# HalfMegCoCo.net
KiCad netlist of a schematic drawn in EAGLE
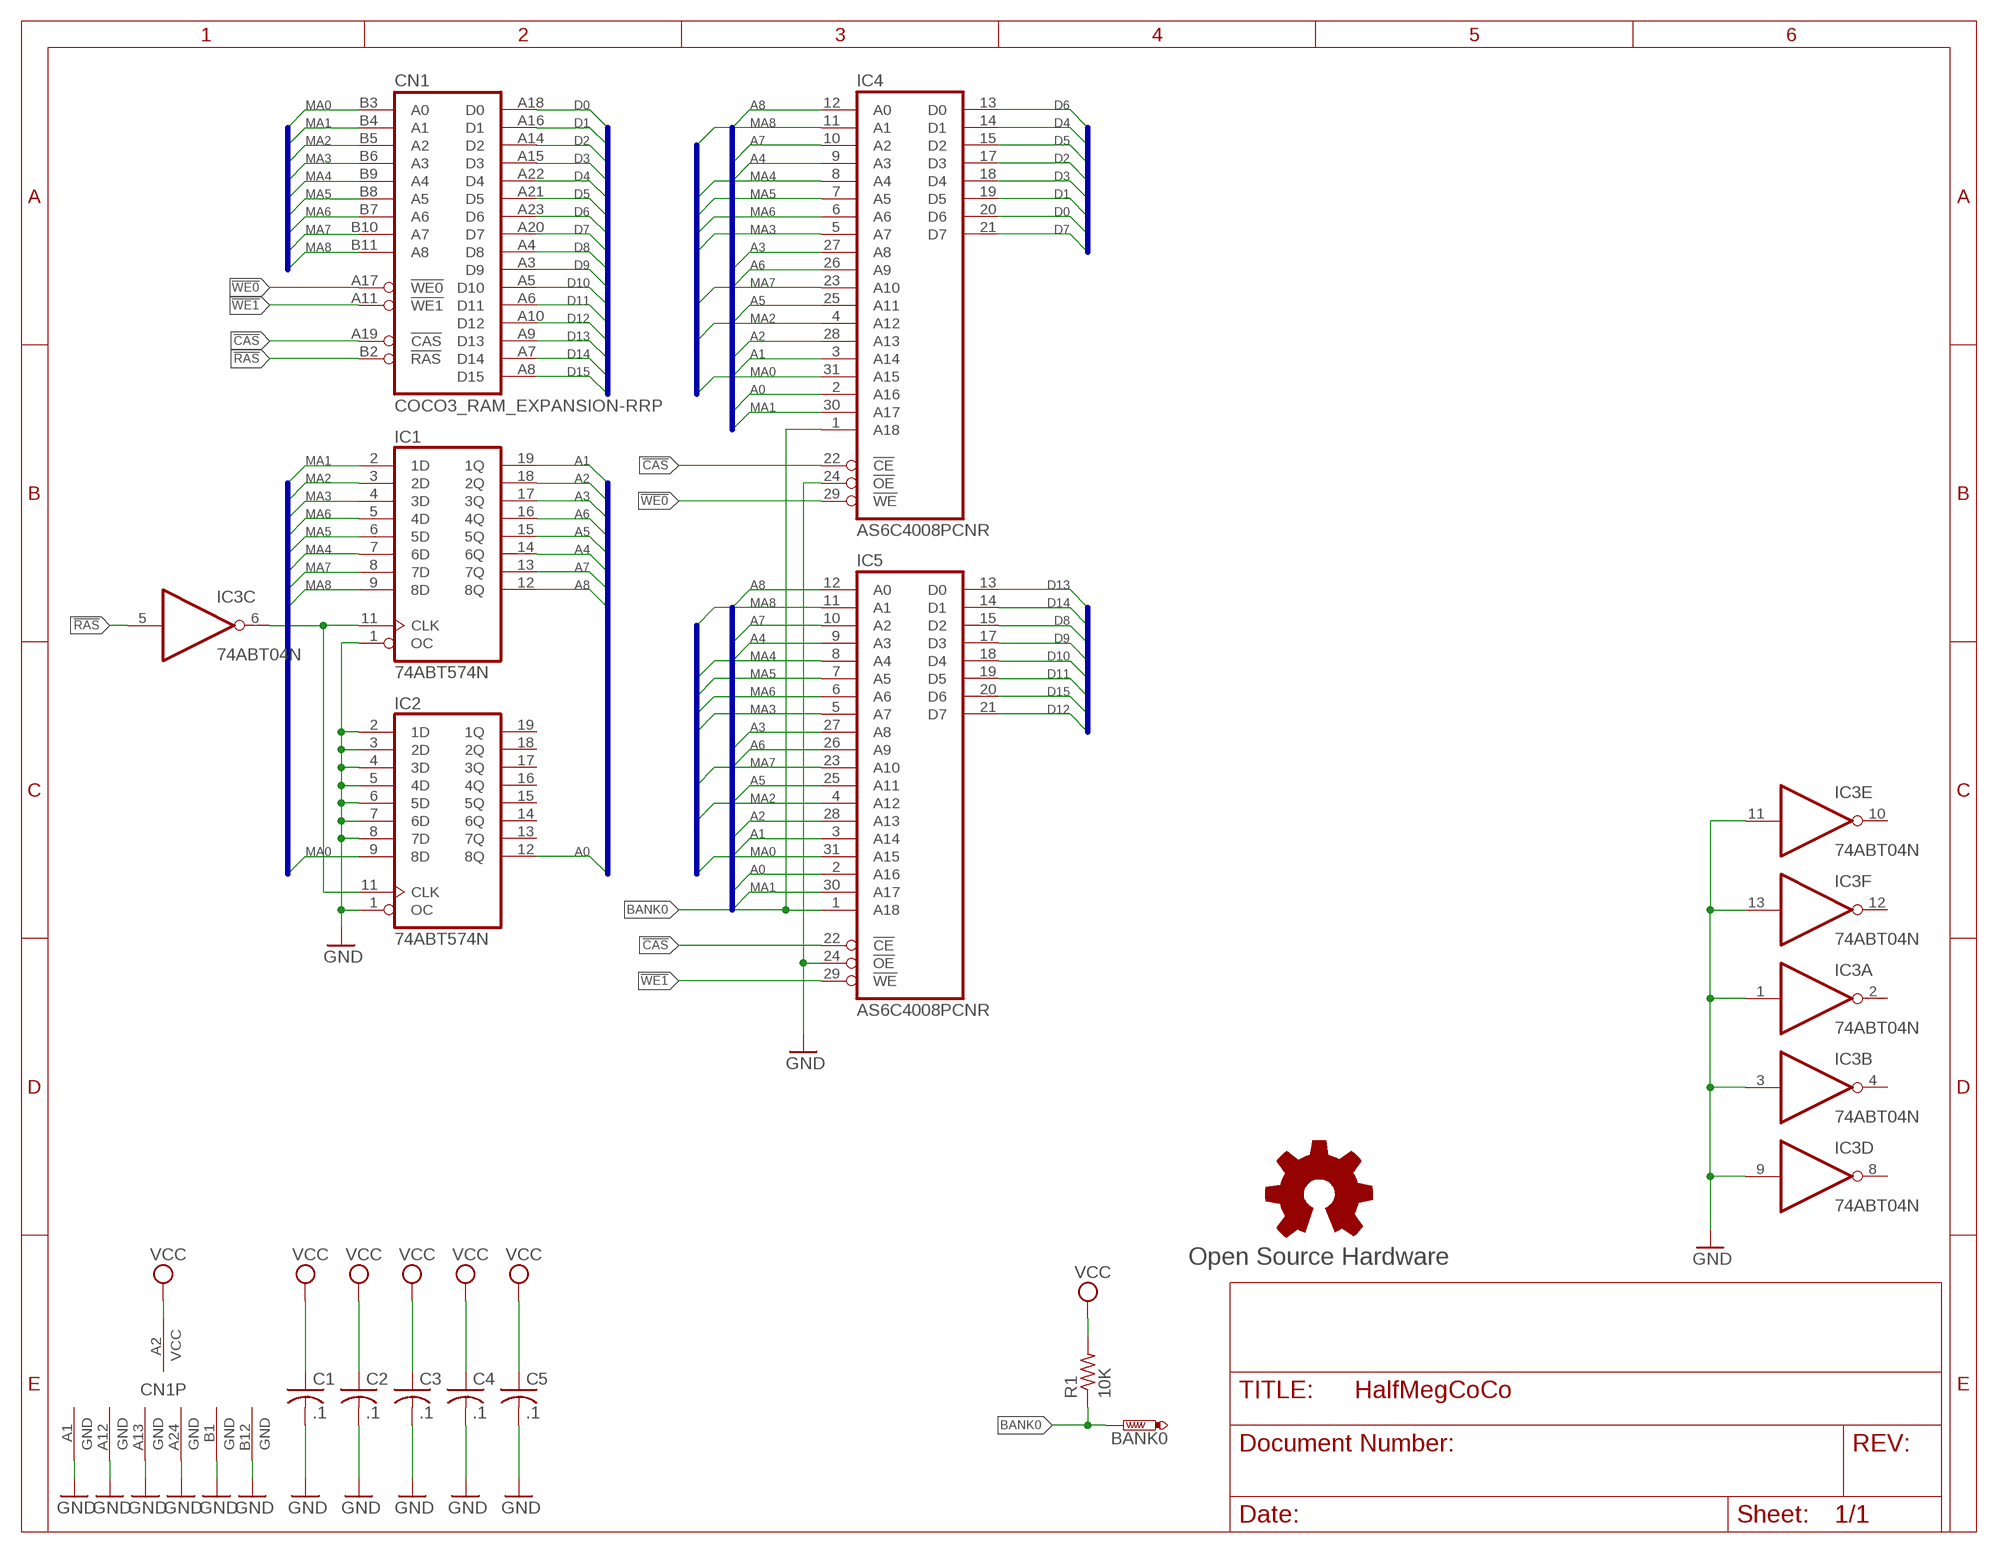
[diagram p0: schematic, sheet 1]

(export (version "E")
  (design (tool "Eeschema 10.0.6"))
  (components
    (comp (ref "BANK0")
      (value "PTR1PAD1-13")
      (footprint "eagle-import:P1-13")
      (libsource (lib "eagle-import") (part "PTR1PAD1-13"))
    )
    (comp (ref "C1")
      (value ".1")
      (footprint "eagle-import:C025-025X050")
      (libsource (lib "eagle-import") (part "C-US025-025X050"))
    )
    (comp (ref "C2")
      (value ".1")
      (footprint "eagle-import:C025-025X050")
      (libsource (lib "eagle-import") (part "C-US025-025X050"))
    )
    (comp (ref "C3")
      (value ".1")
      (footprint "eagle-import:C025-025X050")
      (libsource (lib "eagle-import") (part "C-US025-025X050"))
    )
    (comp (ref "C4")
      (value ".1")
      (footprint "eagle-import:C025-025X050")
      (libsource (lib "eagle-import") (part "C-US025-025X050"))
    )
    (comp (ref "C5")
      (value ".1")
      (footprint "eagle-import:C025-025X050")
      (libsource (lib "eagle-import") (part "C-US025-025X050"))
    )
    (comp (ref "CN1")
      (value "COCO3_RAM_EXPANSION-RRP")
      (footprint "eagle-import:RAM_EXPANSION_REV_RP")
      (libsource (lib "eagle-import") (part "COCO3_RAM_EXPANSION-RRP"))
    )
    (comp (ref "GOLD_ORB_SM1")
      (value "Open Source Hardware")
      (footprint "eagle-import:OSHW_8MM")
      (libsource (lib "eagle-import") (part "OSHWLOGOLOGO8MM"))
    )
    (comp (ref "IC1")
      (value "74ABT574N")
      (footprint "eagle-import:DIL20-RP")
      (libsource (lib "eagle-import") (part "74574NHC"))
    )
    (comp (ref "IC2")
      (value "74ABT574N")
      (footprint "eagle-import:DIL20-RP")
      (libsource (lib "eagle-import") (part "74574NHC"))
    )
    (comp (ref "IC3")
      (value "74ABT04N")
      (footprint "eagle-import:DIL14-RP")
      (libsource (lib "eagle-import") (part "7404NALS"))
    )
    (comp (ref "IC4")
      (value "AS6C4008PCNR")
      (footprint "eagle-import:DIL32-RP")
      (libsource (lib "eagle-import") (part "AS6C4008PCNR"))
    )
    (comp (ref "IC5")
      (value "AS6C4008PCNR")
      (footprint "eagle-import:DIL32-RP")
      (libsource (lib "eagle-import") (part "AS6C4008PCNR"))
    )
    (comp (ref "R1")
      (value "10K")
      (footprint "eagle-import:0204_7")
      (libsource (lib "eagle-import") (part "R-US_0204/7"))
    )
  )
  (nets
    (net (code "1") (name "/A0") (class "Default")
      (node (ref "IC2") (pin "12") (pinfunction "8Q_12") (pintype "tri_state"))
      (node (ref "IC4") (pin "2") (pinfunction "A16_2") (pintype "input"))
      (node (ref "IC5") (pin "2") (pinfunction "A16_2") (pintype "input"))
    )
    (net (code "2") (name "/A1") (class "Default")
      (node (ref "IC1") (pin "19") (pinfunction "1Q_19") (pintype "tri_state"))
      (node (ref "IC4") (pin "3") (pinfunction "A14_3") (pintype "input"))
      (node (ref "IC5") (pin "3") (pinfunction "A14_3") (pintype "input"))
    )
    (net (code "3") (name "/A2") (class "Default")
      (node (ref "IC1") (pin "18") (pinfunction "2Q_18") (pintype "tri_state"))
      (node (ref "IC4") (pin "28") (pinfunction "A13_28") (pintype "input"))
      (node (ref "IC5") (pin "28") (pinfunction "A13_28") (pintype "input"))
    )
    (net (code "4") (name "/A3") (class "Default")
      (node (ref "IC1") (pin "17") (pinfunction "3Q_17") (pintype "tri_state"))
      (node (ref "IC4") (pin "27") (pinfunction "A8_27") (pintype "input"))
      (node (ref "IC5") (pin "27") (pinfunction "A8_27") (pintype "input"))
    )
    (net (code "5") (name "/A4") (class "Default")
      (node (ref "IC1") (pin "14") (pinfunction "6Q_14") (pintype "tri_state"))
      (node (ref "IC4") (pin "9") (pinfunction "A3_9") (pintype "input"))
      (node (ref "IC5") (pin "9") (pinfunction "A3_9") (pintype "input"))
    )
    (net (code "6") (name "/A5") (class "Default")
      (node (ref "IC1") (pin "15") (pinfunction "5Q_15") (pintype "tri_state"))
      (node (ref "IC4") (pin "25") (pinfunction "A11_25") (pintype "input"))
      (node (ref "IC5") (pin "25") (pinfunction "A11_25") (pintype "input"))
    )
    (net (code "7") (name "/A6") (class "Default")
      (node (ref "IC1") (pin "16") (pinfunction "4Q_16") (pintype "tri_state"))
      (node (ref "IC4") (pin "26") (pinfunction "A9_26") (pintype "input"))
      (node (ref "IC5") (pin "26") (pinfunction "A9_26") (pintype "input"))
    )
    (net (code "8") (name "/A7") (class "Default")
      (node (ref "IC1") (pin "13") (pinfunction "7Q_13") (pintype "tri_state"))
      (node (ref "IC4") (pin "10") (pinfunction "A2_10") (pintype "input"))
      (node (ref "IC5") (pin "10") (pinfunction "A2_10") (pintype "input"))
    )
    (net (code "9") (name "/A8") (class "Default")
      (node (ref "IC1") (pin "12") (pinfunction "8Q_12") (pintype "tri_state"))
      (node (ref "IC4") (pin "12") (pinfunction "A0_12") (pintype "input"))
      (node (ref "IC5") (pin "12") (pinfunction "A0_12") (pintype "input"))
    )
    (net (code "10") (name "/D0") (class "Default")
      (node (ref "CN1") (pin "A18") (pinfunction "D0_A18") (pintype "bidirectional"))
      (node (ref "IC4") (pin "20") (pinfunction "D6_20") (pintype "bidirectional"))
    )
    (net (code "11") (name "/D1") (class "Default")
      (node (ref "CN1") (pin "A16") (pinfunction "D1_A16") (pintype "bidirectional"))
      (node (ref "IC4") (pin "19") (pinfunction "D5_19") (pintype "bidirectional"))
    )
    (net (code "12") (name "/D2") (class "Default")
      (node (ref "CN1") (pin "A14") (pinfunction "D2_A14") (pintype "bidirectional"))
      (node (ref "IC4") (pin "17") (pinfunction "D3_17") (pintype "bidirectional"))
    )
    (net (code "13") (name "/D3") (class "Default")
      (node (ref "CN1") (pin "A15") (pinfunction "D3_A15") (pintype "bidirectional"))
      (node (ref "IC4") (pin "18") (pinfunction "D4_18") (pintype "bidirectional"))
    )
    (net (code "14") (name "/D4") (class "Default")
      (node (ref "CN1") (pin "A22") (pinfunction "D4_A22") (pintype "bidirectional"))
      (node (ref "IC4") (pin "14") (pinfunction "D1_14") (pintype "bidirectional"))
    )
    (net (code "15") (name "/D5") (class "Default")
      (node (ref "CN1") (pin "A21") (pinfunction "D5_A21") (pintype "bidirectional"))
      (node (ref "IC4") (pin "15") (pinfunction "D2_15") (pintype "bidirectional"))
    )
    (net (code "16") (name "/D6") (class "Default")
      (node (ref "CN1") (pin "A23") (pinfunction "D6_A23") (pintype "bidirectional"))
      (node (ref "IC4") (pin "13") (pinfunction "D0_13") (pintype "bidirectional"))
    )
    (net (code "17") (name "/D7") (class "Default")
      (node (ref "CN1") (pin "A20") (pinfunction "D7_A20") (pintype "bidirectional"))
      (node (ref "IC4") (pin "21") (pinfunction "D7_21") (pintype "bidirectional"))
    )
    (net (code "18") (name "/D8") (class "Default")
      (node (ref "CN1") (pin "A4") (pinfunction "D8_A4") (pintype "bidirectional"))
      (node (ref "IC5") (pin "15") (pinfunction "D2_15") (pintype "bidirectional"))
    )
    (net (code "19") (name "/D9") (class "Default")
      (node (ref "CN1") (pin "A3") (pinfunction "D9_A3") (pintype "bidirectional"))
      (node (ref "IC5") (pin "17") (pinfunction "D3_17") (pintype "bidirectional"))
    )
    (net (code "20") (name "/D10") (class "Default")
      (node (ref "CN1") (pin "A5") (pinfunction "D10_A5") (pintype "bidirectional"))
      (node (ref "IC5") (pin "18") (pinfunction "D4_18") (pintype "bidirectional"))
    )
    (net (code "21") (name "/D11") (class "Default")
      (node (ref "CN1") (pin "A6") (pinfunction "D11_A6") (pintype "bidirectional"))
      (node (ref "IC5") (pin "19") (pinfunction "D5_19") (pintype "bidirectional"))
    )
    (net (code "22") (name "/D12") (class "Default")
      (node (ref "CN1") (pin "A10") (pinfunction "D12_A10") (pintype "bidirectional"))
      (node (ref "IC5") (pin "21") (pinfunction "D7_21") (pintype "bidirectional"))
    )
    (net (code "23") (name "/D13") (class "Default")
      (node (ref "CN1") (pin "A9") (pinfunction "D13_A9") (pintype "bidirectional"))
      (node (ref "IC5") (pin "13") (pinfunction "D0_13") (pintype "bidirectional"))
    )
    (net (code "24") (name "/D14") (class "Default")
      (node (ref "CN1") (pin "A7") (pinfunction "D14_A7") (pintype "bidirectional"))
      (node (ref "IC5") (pin "14") (pinfunction "D1_14") (pintype "bidirectional"))
    )
    (net (code "25") (name "/D15") (class "Default")
      (node (ref "CN1") (pin "A8") (pinfunction "D15_A8") (pintype "bidirectional"))
      (node (ref "IC5") (pin "20") (pinfunction "D6_20") (pintype "bidirectional"))
    )
    (net (code "26") (name "/MA0") (class "Default")
      (node (ref "CN1") (pin "B3") (pinfunction "A0_B3") (pintype "output"))
      (node (ref "IC2") (pin "9") (pinfunction "8D_9") (pintype "input"))
      (node (ref "IC4") (pin "31") (pinfunction "A15_31") (pintype "input"))
      (node (ref "IC5") (pin "31") (pinfunction "A15_31") (pintype "input"))
    )
    (net (code "27") (name "/MA1") (class "Default")
      (node (ref "CN1") (pin "B4") (pinfunction "A1_B4") (pintype "output"))
      (node (ref "IC1") (pin "2") (pinfunction "1D_2") (pintype "input"))
      (node (ref "IC4") (pin "30") (pinfunction "A17_30") (pintype "input"))
      (node (ref "IC5") (pin "30") (pinfunction "A17_30") (pintype "input"))
    )
    (net (code "28") (name "/MA2") (class "Default")
      (node (ref "CN1") (pin "B5") (pinfunction "A2_B5") (pintype "output"))
      (node (ref "IC1") (pin "3") (pinfunction "2D_3") (pintype "input"))
      (node (ref "IC4") (pin "4") (pinfunction "A12_4") (pintype "input"))
      (node (ref "IC5") (pin "4") (pinfunction "A12_4") (pintype "input"))
    )
    (net (code "29") (name "/MA3") (class "Default")
      (node (ref "CN1") (pin "B6") (pinfunction "A3_B6") (pintype "output"))
      (node (ref "IC1") (pin "4") (pinfunction "3D_4") (pintype "input"))
      (node (ref "IC4") (pin "5") (pinfunction "A7_5") (pintype "input"))
      (node (ref "IC5") (pin "5") (pinfunction "A7_5") (pintype "input"))
    )
    (net (code "30") (name "/MA4") (class "Default")
      (node (ref "CN1") (pin "B9") (pinfunction "A4_B9") (pintype "output"))
      (node (ref "IC1") (pin "7") (pinfunction "6D_7") (pintype "input"))
      (node (ref "IC4") (pin "8") (pinfunction "A4_8") (pintype "input"))
      (node (ref "IC5") (pin "8") (pinfunction "A4_8") (pintype "input"))
    )
    (net (code "31") (name "/MA5") (class "Default")
      (node (ref "CN1") (pin "B8") (pinfunction "A5_B8") (pintype "output"))
      (node (ref "IC1") (pin "6") (pinfunction "5D_6") (pintype "input"))
      (node (ref "IC4") (pin "7") (pinfunction "A5_7") (pintype "input"))
      (node (ref "IC5") (pin "7") (pinfunction "A5_7") (pintype "input"))
    )
    (net (code "32") (name "/MA6") (class "Default")
      (node (ref "CN1") (pin "B7") (pinfunction "A6_B7") (pintype "output"))
      (node (ref "IC1") (pin "5") (pinfunction "4D_5") (pintype "input"))
      (node (ref "IC4") (pin "6") (pinfunction "A6_6") (pintype "input"))
      (node (ref "IC5") (pin "6") (pinfunction "A6_6") (pintype "input"))
    )
    (net (code "33") (name "/MA7") (class "Default")
      (node (ref "CN1") (pin "B10") (pinfunction "A7_B10") (pintype "output"))
      (node (ref "IC1") (pin "8") (pinfunction "7D_8") (pintype "input"))
      (node (ref "IC4") (pin "23") (pinfunction "A10_23") (pintype "input"))
      (node (ref "IC5") (pin "23") (pinfunction "A10_23") (pintype "input"))
    )
    (net (code "34") (name "/MA8") (class "Default")
      (node (ref "CN1") (pin "B11") (pinfunction "A8_B11") (pintype "output"))
      (node (ref "IC1") (pin "9") (pinfunction "8D_9") (pintype "input"))
      (node (ref "IC4") (pin "11") (pinfunction "A1_11") (pintype "input"))
      (node (ref "IC5") (pin "11") (pinfunction "A1_11") (pintype "input"))
    )
    (net (code "35") (name "/~{CAS}") (class "Default")
      (node (ref "CN1") (pin "A19") (pinfunction "~{CAS}_A19") (pintype "output"))
      (node (ref "IC4") (pin "22") (pinfunction "~{CE}_22") (pintype "input"))
      (node (ref "IC5") (pin "22") (pinfunction "~{CE}_22") (pintype "input"))
    )
    (net (code "36") (name "/~{RAS}") (class "Default")
      (node (ref "CN1") (pin "B2") (pinfunction "~{RAS}_B2") (pintype "output"))
      (node (ref "IC3") (pin "5") (pinfunction "I_5") (pintype "input"))
    )
    (net (code "37") (name "/~{WE0}") (class "Default")
      (node (ref "CN1") (pin "A17") (pinfunction "~{WE0}_A17") (pintype "output"))
      (node (ref "IC4") (pin "29") (pinfunction "~{WE}_29") (pintype "input"))
    )
    (net (code "38") (name "/~{WE1}") (class "Default")
      (node (ref "CN1") (pin "A11") (pinfunction "~{WE1}_A11") (pintype "output"))
      (node (ref "IC5") (pin "29") (pinfunction "~{WE}_29") (pintype "input"))
    )
    (net (code "39") (name "BANK0") (class "Default")
      (node (ref "BANK0") (pin "TP") (pinfunction "TP_TP") (pintype "input"))
      (node (ref "IC4") (pin "1") (pinfunction "A18_1") (pintype "input"))
      (node (ref "IC5") (pin "1") (pinfunction "A18_1") (pintype "input"))
      (node (ref "R1") (pin "1") (pinfunction "1_1") (pintype "passive"))
    )
    (net (code "40") (name "GND") (class "Default")
      (node (ref "C1") (pin "2") (pinfunction "2_2") (pintype "passive"))
      (node (ref "C2") (pin "2") (pinfunction "2_2") (pintype "passive"))
      (node (ref "C3") (pin "2") (pinfunction "2_2") (pintype "passive"))
      (node (ref "C4") (pin "2") (pinfunction "2_2") (pintype "passive"))
      (node (ref "C5") (pin "2") (pinfunction "2_2") (pintype "passive"))
      (node (ref "CN1") (pin "A1") (pinfunction "GND_A1") (pintype "power_in"))
      (node (ref "CN1") (pin "A12") (pinfunction "GND_A12") (pintype "power_in"))
      (node (ref "CN1") (pin "A13") (pinfunction "GND_A13") (pintype "power_in"))
      (node (ref "CN1") (pin "A24") (pinfunction "GND_A24") (pintype "power_in"))
      (node (ref "CN1") (pin "B1") (pinfunction "GND_B1") (pintype "power_in"))
      (node (ref "CN1") (pin "B12") (pinfunction "GND_B12") (pintype "power_in"))
      (node (ref "IC1") (pin "1") (pinfunction "OC_1") (pintype "input"))
      (node (ref "IC2") (pin "1") (pinfunction "OC_1") (pintype "input"))
      (node (ref "IC2") (pin "2") (pinfunction "1D_2") (pintype "input"))
      (node (ref "IC2") (pin "3") (pinfunction "2D_3") (pintype "input"))
      (node (ref "IC2") (pin "4") (pinfunction "3D_4") (pintype "input"))
      (node (ref "IC2") (pin "5") (pinfunction "4D_5") (pintype "input"))
      (node (ref "IC2") (pin "6") (pinfunction "5D_6") (pintype "input"))
      (node (ref "IC2") (pin "7") (pinfunction "6D_7") (pintype "input"))
      (node (ref "IC2") (pin "8") (pinfunction "7D_8") (pintype "input"))
      (node (ref "IC3") (pin "1") (pinfunction "I_1") (pintype "input"))
      (node (ref "IC3") (pin "11") (pinfunction "I_11") (pintype "input"))
      (node (ref "IC3") (pin "13") (pinfunction "I_13") (pintype "input"))
      (node (ref "IC3") (pin "3") (pinfunction "I_3") (pintype "input"))
      (node (ref "IC3") (pin "9") (pinfunction "I_9") (pintype "input"))
      (node (ref "IC4") (pin "24") (pinfunction "~{OE}_24") (pintype "input"))
      (node (ref "IC5") (pin "24") (pinfunction "~{OE}_24") (pintype "input"))
    )
    (net (code "41") (name "Net-(IC1A-CLK)") (class "Default")
      (node (ref "IC1") (pin "11") (pinfunction "CLK_11") (pintype "input"))
      (node (ref "IC2") (pin "11") (pinfunction "CLK_11") (pintype "input"))
      (node (ref "IC3") (pin "6") (pinfunction "O_6") (pintype "output"))
    )
    (net (code "42") (name "VCC") (class "Default")
      (node (ref "C1") (pin "1") (pinfunction "1_1") (pintype "passive"))
      (node (ref "C2") (pin "1") (pinfunction "1_1") (pintype "passive"))
      (node (ref "C3") (pin "1") (pinfunction "1_1") (pintype "passive"))
      (node (ref "C4") (pin "1") (pinfunction "1_1") (pintype "passive"))
      (node (ref "C5") (pin "1") (pinfunction "1_1") (pintype "passive"))
      (node (ref "CN1") (pin "A2") (pinfunction "VCC_A2") (pintype "power_in"))
      (node (ref "R1") (pin "2") (pinfunction "2_2") (pintype "passive"))
    )
    (net (code "43") (name "unconnected-(IC2A-1Q-Pad19)") (class "Default")
      (node (ref "IC2") (pin "19") (pinfunction "1Q_19") (pintype "tri_state"))
    )
    (net (code "44") (name "unconnected-(IC2A-2Q-Pad18)") (class "Default")
      (node (ref "IC2") (pin "18") (pinfunction "2Q_18") (pintype "tri_state"))
    )
    (net (code "45") (name "unconnected-(IC2A-3Q-Pad17)") (class "Default")
      (node (ref "IC2") (pin "17") (pinfunction "3Q_17") (pintype "tri_state"))
    )
    (net (code "46") (name "unconnected-(IC2A-4Q-Pad16)") (class "Default")
      (node (ref "IC2") (pin "16") (pinfunction "4Q_16") (pintype "tri_state"))
    )
    (net (code "47") (name "unconnected-(IC2A-5Q-Pad15)") (class "Default")
      (node (ref "IC2") (pin "15") (pinfunction "5Q_15") (pintype "tri_state"))
    )
    (net (code "48") (name "unconnected-(IC2A-6Q-Pad14)") (class "Default")
      (node (ref "IC2") (pin "14") (pinfunction "6Q_14") (pintype "tri_state"))
    )
    (net (code "49") (name "unconnected-(IC2A-7Q-Pad13)") (class "Default")
      (node (ref "IC2") (pin "13") (pinfunction "7Q_13") (pintype "tri_state"))
    )
    (net (code "50") (name "unconnected-(IC3A-O-Pad2)") (class "Default")
      (node (ref "IC3") (pin "2") (pinfunction "O_2") (pintype "output"))
    )
    (net (code "51") (name "unconnected-(IC3B-O-Pad4)") (class "Default")
      (node (ref "IC3") (pin "4") (pinfunction "O_4") (pintype "output"))
    )
    (net (code "52") (name "unconnected-(IC3D-O-Pad8)") (class "Default")
      (node (ref "IC3") (pin "8") (pinfunction "O_8") (pintype "output"))
    )
    (net (code "53") (name "unconnected-(IC3E-O-Pad10)") (class "Default")
      (node (ref "IC3") (pin "10") (pinfunction "O_10") (pintype "output"))
    )
    (net (code "54") (name "unconnected-(IC3F-O-Pad12)") (class "Default")
      (node (ref "IC3") (pin "12") (pinfunction "O_12") (pintype "output"))
    )
  )
)
